# Chest_ECG.net
KiCad netlist of a schematic drawn in EAGLE
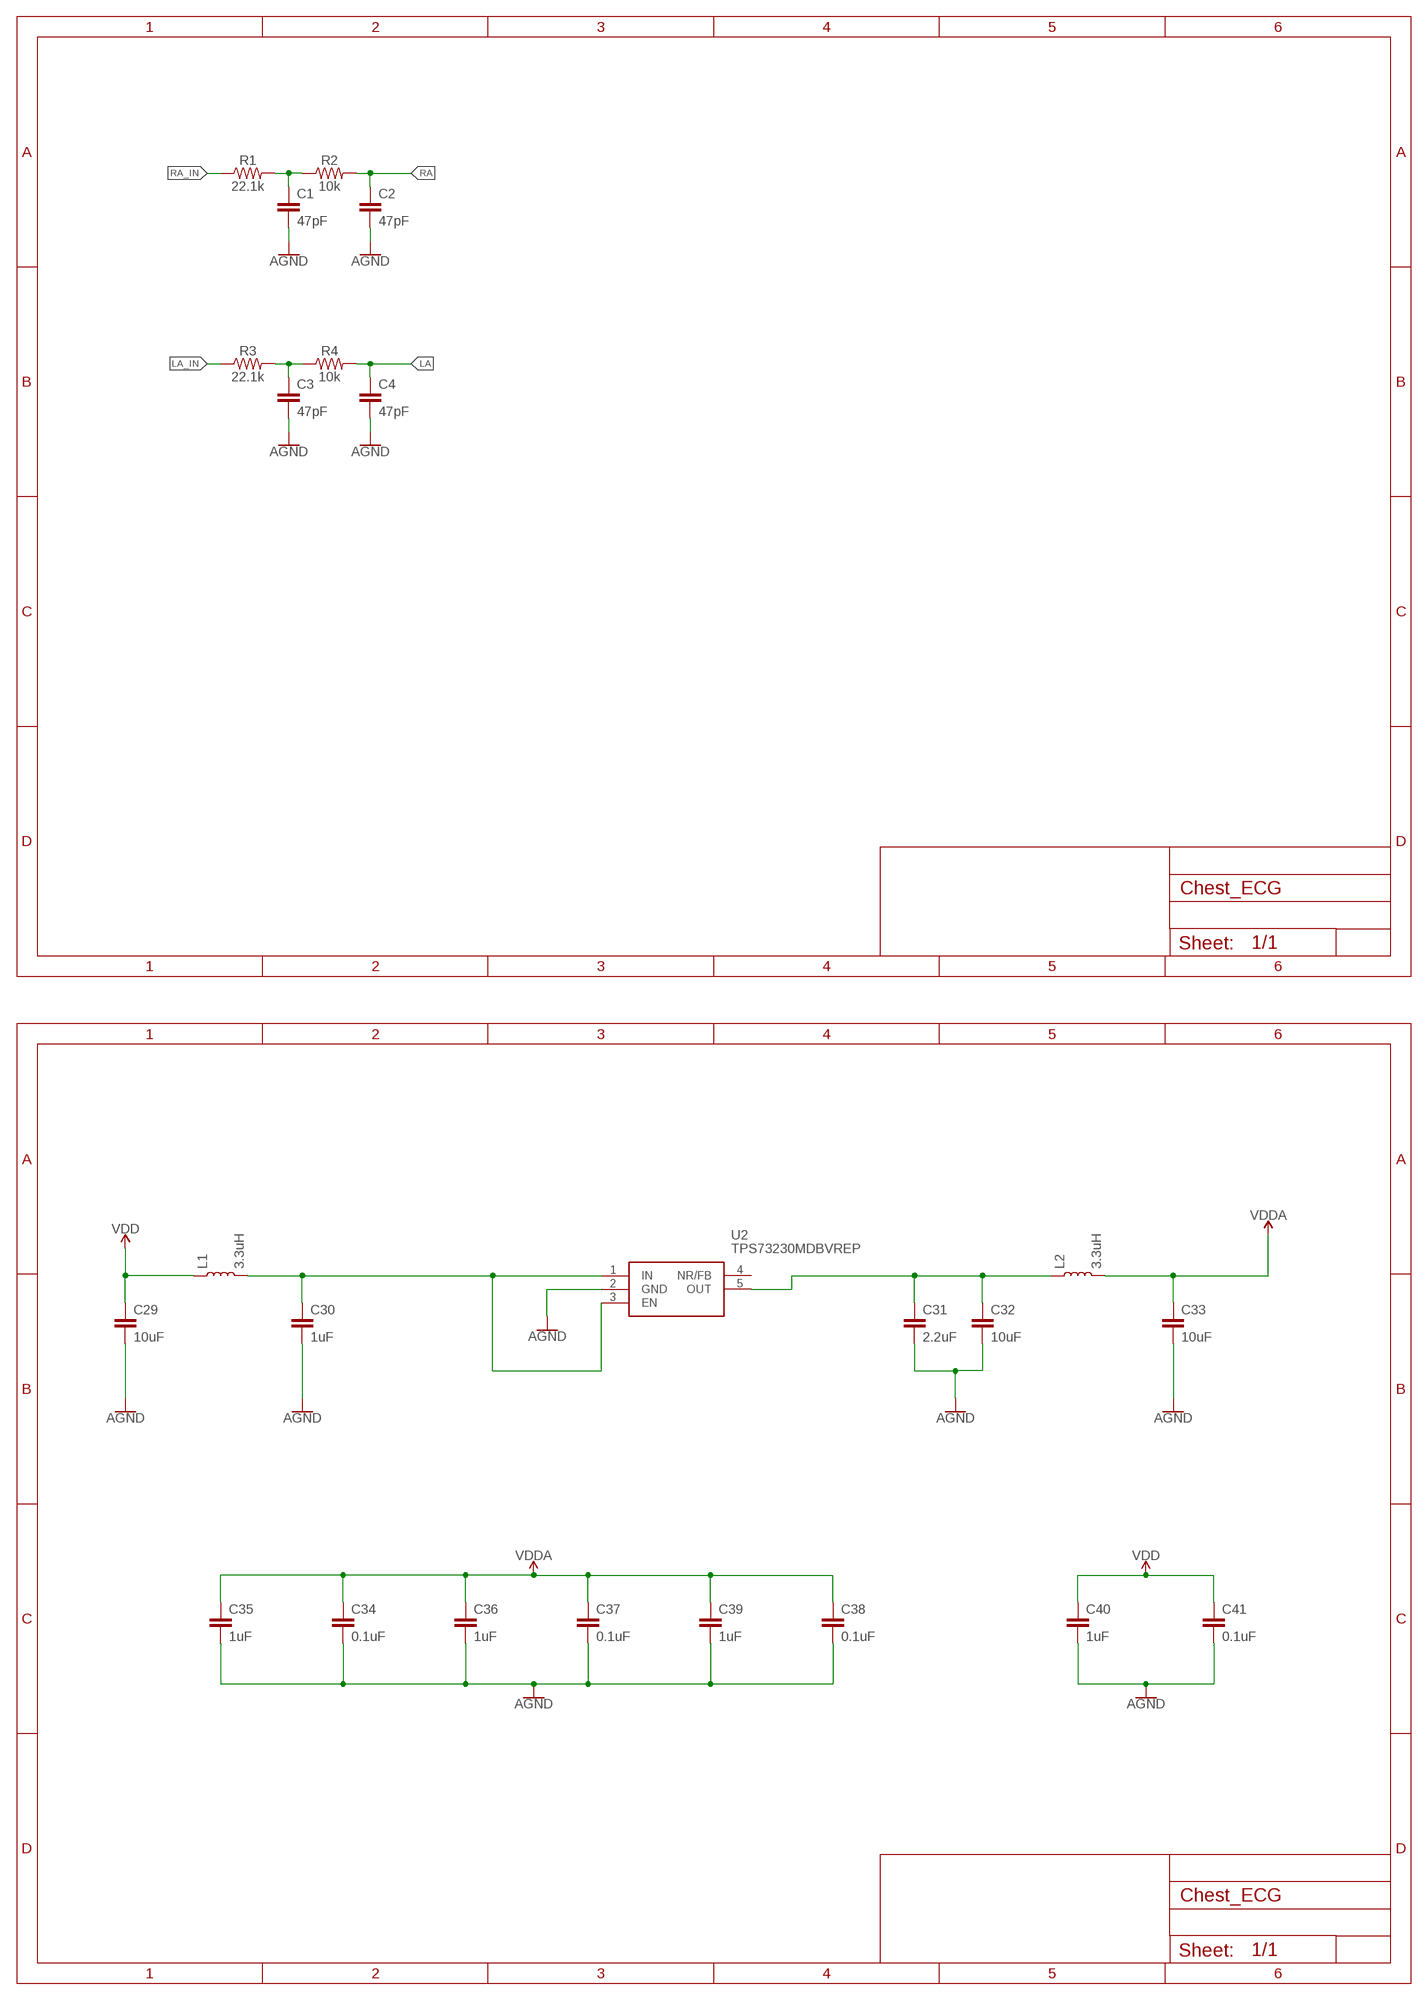
[diagram p0: schematic, sheet 1, part 1 of 2]
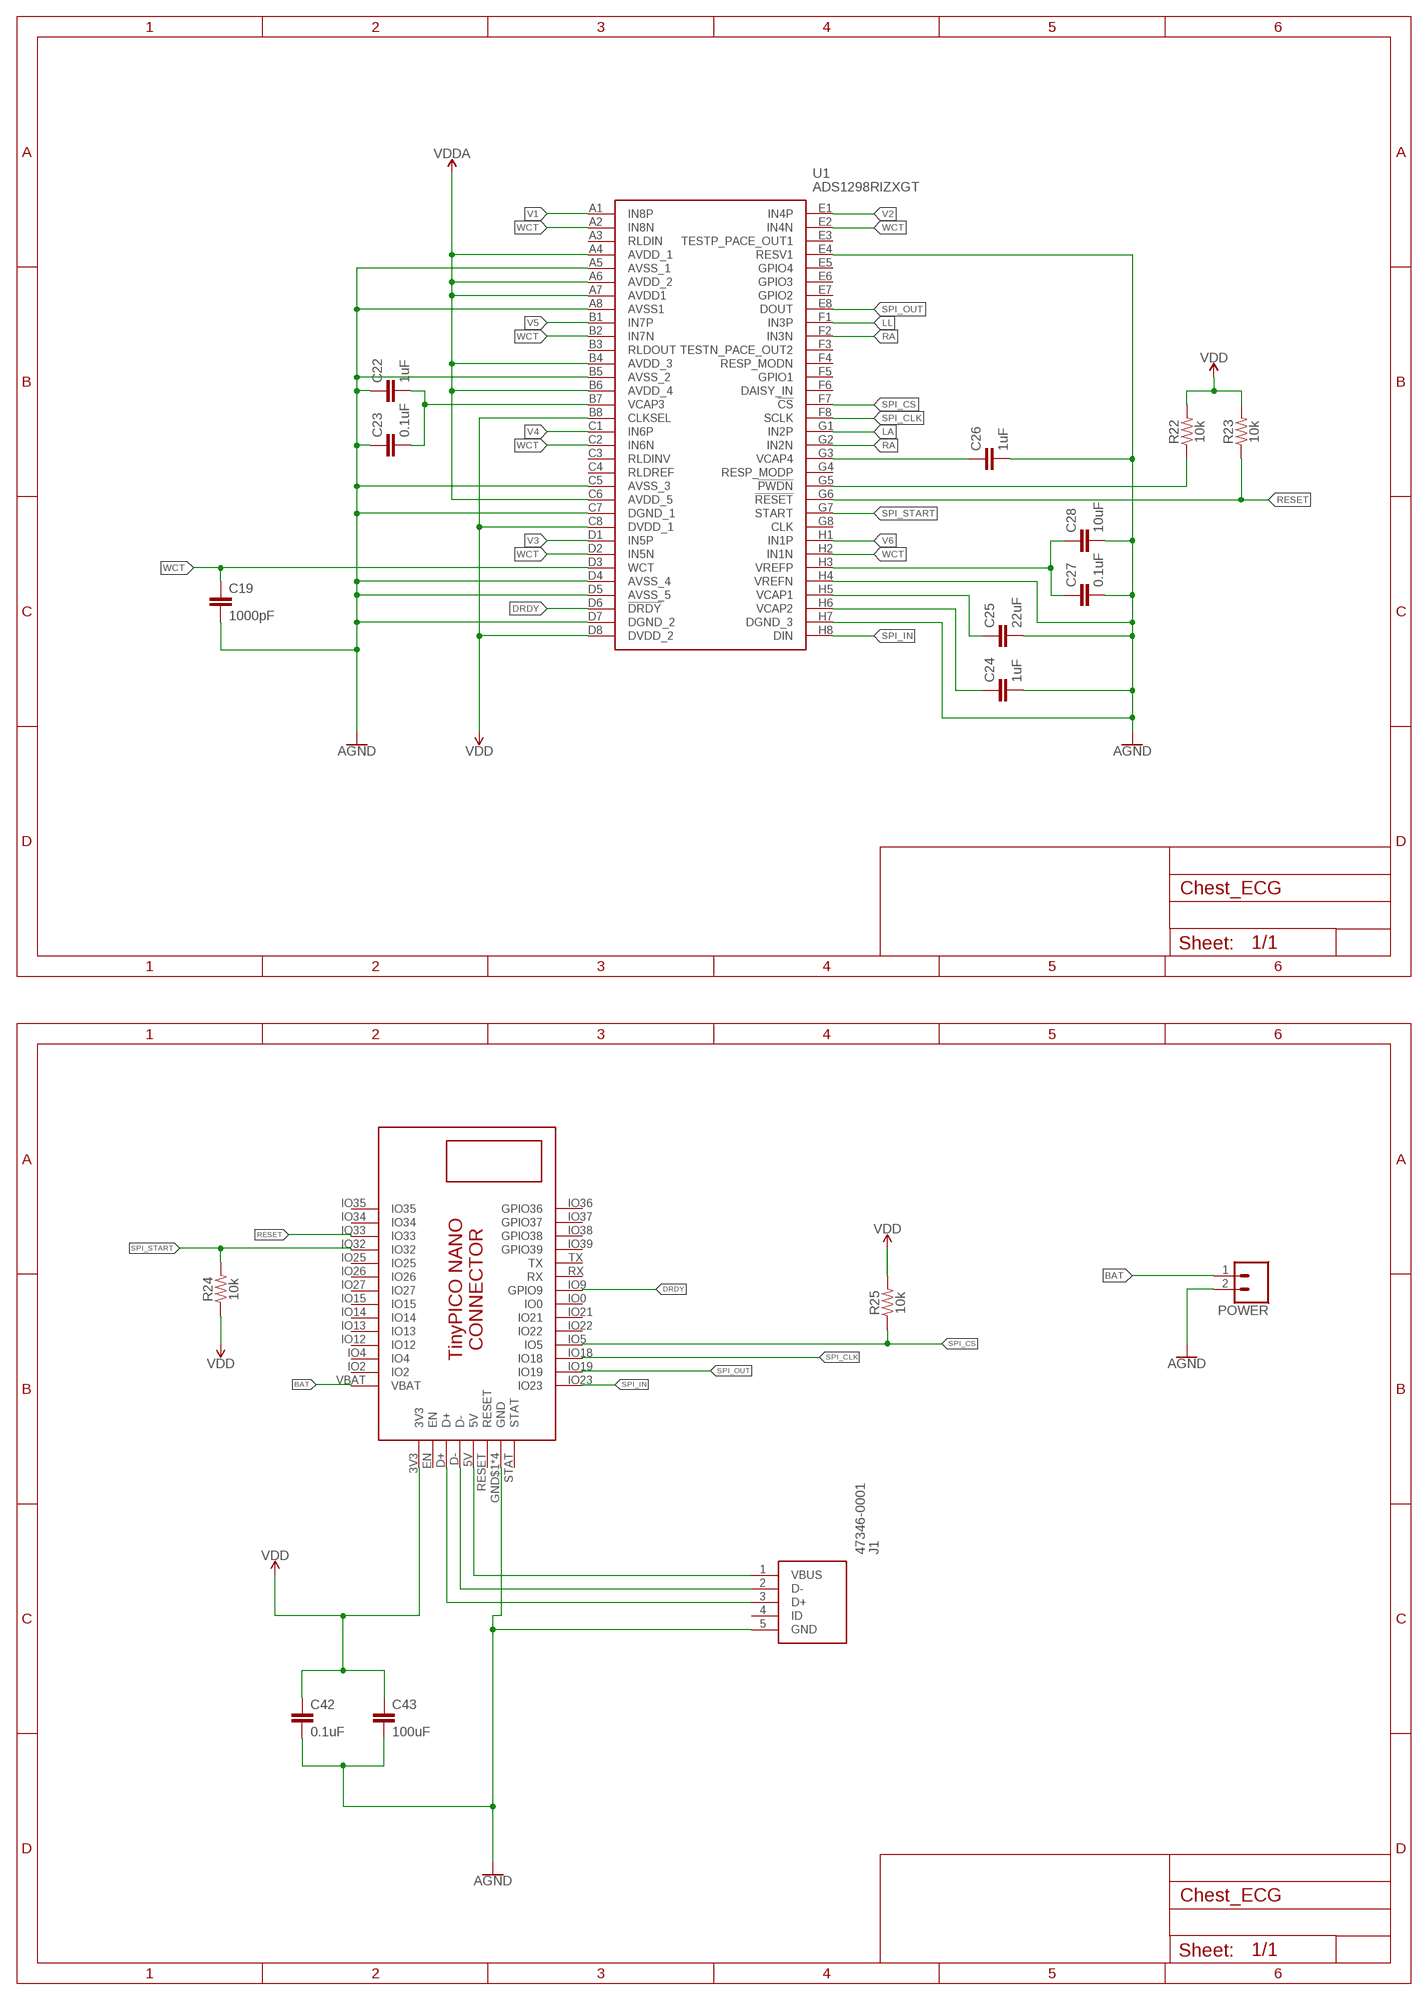
[diagram p1: schematic, sheet 1, part 2 of 2]

(export (version "E")
  (design (tool "Eeschema 10.0.6"))
  (components
    (comp (ref "C1")
      (value "47pF")
      (footprint "eagle-import:0603")
      (libsource (lib "eagle-import") (part "CAP-0603"))
    )
    (comp (ref "C2")
      (value "47pF")
      (footprint "eagle-import:0603")
      (libsource (lib "eagle-import") (part "CAP-0603"))
    )
    (comp (ref "C3")
      (value "47pF")
      (footprint "eagle-import:0603")
      (libsource (lib "eagle-import") (part "CAP-0603"))
    )
    (comp (ref "C4")
      (value "47pF")
      (footprint "eagle-import:0603")
      (libsource (lib "eagle-import") (part "CAP-0603"))
    )
    (comp (ref "C19")
      (value "1000pF")
      (footprint "eagle-import:0603")
      (libsource (lib "eagle-import") (part "CAP-0603"))
    )
    (comp (ref "C22")
      (value "1uF")
      (footprint "eagle-import:0603")
      (libsource (lib "eagle-import") (part "CAP-0603"))
    )
    (comp (ref "C23")
      (value "0.1uF")
      (footprint "eagle-import:0603")
      (libsource (lib "eagle-import") (part "CAP-0603"))
    )
    (comp (ref "C24")
      (value "1uF")
      (footprint "eagle-import:0603")
      (libsource (lib "eagle-import") (part "CAP-0603"))
    )
    (comp (ref "C25")
      (value "22uF")
      (footprint "eagle-import:0805")
      (libsource (lib "eagle-import") (part "CAP-0805"))
    )
    (comp (ref "C26")
      (value "1uF")
      (footprint "eagle-import:0603")
      (libsource (lib "eagle-import") (part "CAP-0603"))
    )
    (comp (ref "C27")
      (value "0.1uF")
      (footprint "eagle-import:0603")
      (libsource (lib "eagle-import") (part "CAP-0603"))
    )
    (comp (ref "C28")
      (value "10uF")
      (footprint "eagle-import:0805")
      (libsource (lib "eagle-import") (part "CAP-0805"))
    )
    (comp (ref "C29")
      (value "10uF")
      (footprint "eagle-import:0805")
      (libsource (lib "eagle-import") (part "CAP-0805"))
    )
    (comp (ref "C30")
      (value "1uF")
      (footprint "eagle-import:0603")
      (libsource (lib "eagle-import") (part "CAP-0603"))
    )
    (comp (ref "C31")
      (value "2.2uF")
      (footprint "eagle-import:0603")
      (libsource (lib "eagle-import") (part "CAP-0603"))
    )
    (comp (ref "C32")
      (value "10uF")
      (footprint "eagle-import:0805")
      (libsource (lib "eagle-import") (part "CAP-0805"))
    )
    (comp (ref "C33")
      (value "10uF")
      (footprint "eagle-import:0805")
      (libsource (lib "eagle-import") (part "CAP-0805"))
    )
    (comp (ref "C34")
      (value "0.1uF")
      (footprint "eagle-import:0603")
      (libsource (lib "eagle-import") (part "CAP-0603"))
    )
    (comp (ref "C35")
      (value "1uF")
      (footprint "eagle-import:0603")
      (libsource (lib "eagle-import") (part "CAP-0603"))
    )
    (comp (ref "C36")
      (value "1uF")
      (footprint "eagle-import:0603")
      (libsource (lib "eagle-import") (part "CAP-0603"))
    )
    (comp (ref "C37")
      (value "0.1uF")
      (footprint "eagle-import:0603")
      (libsource (lib "eagle-import") (part "CAP-0603"))
    )
    (comp (ref "C38")
      (value "0.1uF")
      (footprint "eagle-import:0603")
      (libsource (lib "eagle-import") (part "CAP-0603"))
    )
    (comp (ref "C39")
      (value "1uF")
      (footprint "eagle-import:0603")
      (libsource (lib "eagle-import") (part "CAP-0603"))
    )
    (comp (ref "C40")
      (value "1uF")
      (footprint "eagle-import:0603")
      (libsource (lib "eagle-import") (part "CAP-0603"))
    )
    (comp (ref "C41")
      (value "0.1uF")
      (footprint "eagle-import:0603")
      (libsource (lib "eagle-import") (part "CAP-0603"))
    )
    (comp (ref "C42")
      (value "0.1uF")
      (footprint "eagle-import:0603")
      (libsource (lib "eagle-import") (part "CAP-0603"))
    )
    (comp (ref "C43")
      (value "100uF")
      (footprint "eagle-import:0805")
      (libsource (lib "eagle-import") (part "CAP-0805"))
    )
    (comp (ref "J1")
      (value "47346-0001")
      (footprint "eagle-import:47346-0001")
      (fields (field (name "MOUSER_PART_NUMBER") "538-47346-0001"))
      (libsource (lib "eagle-import") (part "47346-0001"))
    )
    (comp (ref "L1")
      (value "3.3uH")
      (footprint "eagle-import:0805")
      (libsource (lib "eagle-import") (part "INDUCTOR-0805-3.3UH"))
    )
    (comp (ref "L2")
      (value "3.3uH")
      (footprint "eagle-import:0805")
      (libsource (lib "eagle-import") (part "INDUCTOR-0805-3.3UH"))
    )
    (comp (ref "POWER")
      (value "CONN_02")
      (footprint "eagle-import:1X02")
      (libsource (lib "eagle-import") (part "CONN_02"))
    )
    (comp (ref "R1")
      (value "22.1k")
      (footprint "eagle-import:0603")
      (libsource (lib "eagle-import") (part "RESISTOR0603"))
    )
    (comp (ref "R2")
      (value "10k")
      (footprint "eagle-import:0603")
      (libsource (lib "eagle-import") (part "RESISTOR0603"))
    )
    (comp (ref "R3")
      (value "22.1k")
      (footprint "eagle-import:0603")
      (libsource (lib "eagle-import") (part "RESISTOR0603"))
    )
    (comp (ref "R4")
      (value "10k")
      (footprint "eagle-import:0603")
      (libsource (lib "eagle-import") (part "RESISTOR0603"))
    )
    (comp (ref "R22")
      (value "10k")
      (footprint "eagle-import:0603")
      (libsource (lib "eagle-import") (part "RESISTOR0603"))
    )
    (comp (ref "R23")
      (value "10k")
      (footprint "eagle-import:0603")
      (libsource (lib "eagle-import") (part "RESISTOR0603"))
    )
    (comp (ref "R24")
      (value "10k")
      (footprint "eagle-import:0603")
      (libsource (lib "eagle-import") (part "RESISTOR0603"))
    )
    (comp (ref "R25")
      (value "10k")
      (footprint "eagle-import:0603")
      (libsource (lib "eagle-import") (part "RESISTOR0603"))
    )
    (comp (ref "U1")
      (value "ADS1298RIZXGT")
      (footprint "eagle-import:BGA64C80P8X8_800X800X145")
      (fields (field (name "MOUSER_PART_NUMBER") "595-ADS1298RIZXGT"))
      (libsource (lib "eagle-import") (part "ADS1298RIZXGT"))
    )
    (comp (ref "U2")
      (value "TPS73230MDBVREP")
      (footprint "eagle-import:SOT95P280X145-5N")
      (fields (field (name "MOUSER_PART_NUMBER") "595-TPS73230MDBVREP"))
      (libsource (lib "eagle-import") (part "TPS73230MDBVREP"))
    )
    (comp (ref "U3")
      (value "TINYPICO-NANO-CONNECTOR")
      (footprint "eagle-import:TINYPICO-NANO-CONNECTOR")
      (libsource (lib "eagle-import") (part "TINYPICO-NANO-CONNECTOR"))
    )
  )
  (nets
    (net (code "1") (name "AGND") (class "Default")
      (node (ref "C1") (pin "2") (pinfunction "2_2") (pintype "passive"))
      (node (ref "C19") (pin "2") (pinfunction "2_2") (pintype "passive"))
      (node (ref "C2") (pin "2") (pinfunction "2_2") (pintype "passive"))
      (node (ref "C22") (pin "1") (pinfunction "1_1") (pintype "passive"))
      (node (ref "C23") (pin "1") (pinfunction "1_1") (pintype "passive"))
      (node (ref "C24") (pin "2") (pinfunction "2_2") (pintype "passive"))
      (node (ref "C25") (pin "2") (pinfunction "2_2") (pintype "passive"))
      (node (ref "C26") (pin "2") (pinfunction "2_2") (pintype "passive"))
      (node (ref "C27") (pin "2") (pinfunction "2_2") (pintype "passive"))
      (node (ref "C28") (pin "2") (pinfunction "2_2") (pintype "passive"))
      (node (ref "C29") (pin "2") (pinfunction "2_2") (pintype "passive"))
      (node (ref "C3") (pin "2") (pinfunction "2_2") (pintype "passive"))
      (node (ref "C30") (pin "2") (pinfunction "2_2") (pintype "passive"))
      (node (ref "C31") (pin "2") (pinfunction "2_2") (pintype "passive"))
      (node (ref "C32") (pin "2") (pinfunction "2_2") (pintype "passive"))
      (node (ref "C33") (pin "2") (pinfunction "2_2") (pintype "passive"))
      (node (ref "C34") (pin "2") (pinfunction "2_2") (pintype "passive"))
      (node (ref "C35") (pin "2") (pinfunction "2_2") (pintype "passive"))
      (node (ref "C36") (pin "2") (pinfunction "2_2") (pintype "passive"))
      (node (ref "C37") (pin "2") (pinfunction "2_2") (pintype "passive"))
      (node (ref "C38") (pin "2") (pinfunction "2_2") (pintype "passive"))
      (node (ref "C39") (pin "2") (pinfunction "2_2") (pintype "passive"))
      (node (ref "C4") (pin "2") (pinfunction "2_2") (pintype "passive"))
      (node (ref "C40") (pin "2") (pinfunction "2_2") (pintype "passive"))
      (node (ref "C41") (pin "2") (pinfunction "2_2") (pintype "passive"))
      (node (ref "C42") (pin "2") (pinfunction "2_2") (pintype "passive"))
      (node (ref "C43") (pin "2") (pinfunction "2_2") (pintype "passive"))
      (node (ref "J1") (pin "5") (pinfunction "GND_5") (pintype "bidirectional"))
      (node (ref "POWER") (pin "2") (pinfunction "2_2") (pintype "passive"))
      (node (ref "U1") (pin "A5") (pinfunction "AVSS_1_A5") (pintype "bidirectional"))
      (node (ref "U1") (pin "A8") (pinfunction "AVSS1_A8") (pintype "bidirectional"))
      (node (ref "U1") (pin "B5") (pinfunction "AVSS_2_B5") (pintype "bidirectional"))
      (node (ref "U1") (pin "C5") (pinfunction "AVSS_3_C5") (pintype "bidirectional"))
      (node (ref "U1") (pin "C7") (pinfunction "DGND_1_C7") (pintype "bidirectional"))
      (node (ref "U1") (pin "D4") (pinfunction "AVSS_4_D4") (pintype "bidirectional"))
      (node (ref "U1") (pin "D5") (pinfunction "AVSS_5_D5") (pintype "bidirectional"))
      (node (ref "U1") (pin "D7") (pinfunction "DGND_2_D7") (pintype "bidirectional"))
      (node (ref "U1") (pin "E4") (pinfunction "RESV1_E4") (pintype "bidirectional"))
      (node (ref "U1") (pin "H4") (pinfunction "VREFN_H4") (pintype "bidirectional"))
      (node (ref "U1") (pin "H7") (pinfunction "DGND_3_H7") (pintype "bidirectional"))
      (node (ref "U2") (pin "2") (pinfunction "GND_2") (pintype "bidirectional"))
      (node (ref "U3") (pin "GND$1") (pinfunction "GND_GND$1") (pintype "power_in"))
      (node (ref "U3") (pin "GND$2") (pinfunction "GND_GND$2") (pintype "power_in"))
      (node (ref "U3") (pin "GND$3") (pinfunction "GND_GND$3") (pintype "power_in"))
      (node (ref "U3") (pin "GND$4") (pinfunction "GND_GND$4") (pintype "power_in"))
    )
    (net (code "2") (name "BAT") (class "Default")
      (node (ref "POWER") (pin "1") (pinfunction "1_1") (pintype "passive"))
      (node (ref "U3") (pin "VBAT") (pinfunction "VBAT_VBAT") (pintype "power_in"))
    )
    (net (code "3") (name "DRDY") (class "Default")
      (node (ref "U1") (pin "D6") (pinfunction "~{DRDY}_D6") (pintype "bidirectional"))
      (node (ref "U3") (pin "IO9") (pinfunction "GPIO9_IO9") (pintype "bidirectional"))
    )
    (net (code "4") (name "LA") (class "Default")
      (node (ref "C4") (pin "1") (pinfunction "1_1") (pintype "passive"))
      (node (ref "R4") (pin "2") (pinfunction "2_2") (pintype "passive"))
      (node (ref "U1") (pin "G1") (pinfunction "IN2P_G1") (pintype "bidirectional"))
    )
    (net (code "5") (name "LA_IN") (class "Default")
      (node (ref "R3") (pin "1") (pinfunction "1_1") (pintype "passive"))
    )
    (net (code "6") (name "LL") (class "Default")
      (node (ref "U1") (pin "F1") (pinfunction "IN3P_F1") (pintype "bidirectional"))
    )
    (net (code "7") (name "Net-(C1-Pad1)") (class "Default")
      (node (ref "C1") (pin "1") (pinfunction "1_1") (pintype "passive"))
      (node (ref "R1") (pin "2") (pinfunction "2_2") (pintype "passive"))
      (node (ref "R2") (pin "1") (pinfunction "1_1") (pintype "passive"))
    )
    (net (code "8") (name "Net-(C3-Pad1)") (class "Default")
      (node (ref "C3") (pin "1") (pinfunction "1_1") (pintype "passive"))
      (node (ref "R3") (pin "2") (pinfunction "2_2") (pintype "passive"))
      (node (ref "R4") (pin "1") (pinfunction "1_1") (pintype "passive"))
    )
    (net (code "9") (name "Net-(J1-D+)") (class "Default")
      (node (ref "J1") (pin "3") (pinfunction "D+_3") (pintype "bidirectional"))
      (node (ref "U3") (pin "D+") (pinfunction "D+_D+") (pintype "bidirectional"))
    )
    (net (code "10") (name "Net-(J1-D-)") (class "Default")
      (node (ref "J1") (pin "2") (pinfunction "D-_2") (pintype "bidirectional"))
      (node (ref "U3") (pin "D-") (pinfunction "D-_D-") (pintype "bidirectional"))
    )
    (net (code "11") (name "Net-(J1-VBUS)") (class "Default")
      (node (ref "J1") (pin "1") (pinfunction "VBUS_1") (pintype "bidirectional"))
      (node (ref "U3") (pin "5V") (pinfunction "5V_5V") (pintype "power_in"))
    )
    (net (code "12") (name "Net-(U1-VCAP1)") (class "Default")
      (node (ref "C25") (pin "1") (pinfunction "1_1") (pintype "passive"))
      (node (ref "U1") (pin "H5") (pinfunction "VCAP1_H5") (pintype "bidirectional"))
    )
    (net (code "13") (name "Net-(U1-VCAP2)") (class "Default")
      (node (ref "C24") (pin "1") (pinfunction "1_1") (pintype "passive"))
      (node (ref "U1") (pin "H6") (pinfunction "VCAP2_H6") (pintype "bidirectional"))
    )
    (net (code "14") (name "Net-(U1-VCAP3)") (class "Default")
      (node (ref "C22") (pin "2") (pinfunction "2_2") (pintype "passive"))
      (node (ref "C23") (pin "2") (pinfunction "2_2") (pintype "passive"))
      (node (ref "U1") (pin "B7") (pinfunction "VCAP3_B7") (pintype "bidirectional"))
    )
    (net (code "15") (name "Net-(U1-VCAP4)") (class "Default")
      (node (ref "C26") (pin "1") (pinfunction "1_1") (pintype "passive"))
      (node (ref "U1") (pin "G3") (pinfunction "VCAP4_G3") (pintype "bidirectional"))
    )
    (net (code "16") (name "Net-(U1-VREFP)") (class "Default")
      (node (ref "C27") (pin "1") (pinfunction "1_1") (pintype "passive"))
      (node (ref "C28") (pin "1") (pinfunction "1_1") (pintype "passive"))
      (node (ref "U1") (pin "H3") (pinfunction "VREFP_H3") (pintype "bidirectional"))
    )
    (net (code "17") (name "Net-(U1-~{PWDN})") (class "Default")
      (node (ref "R22") (pin "1") (pinfunction "1_1") (pintype "passive"))
      (node (ref "U1") (pin "G5") (pinfunction "~{PWDN}_G5") (pintype "bidirectional"))
    )
    (net (code "18") (name "Net-(U2-EN)") (class "Default")
      (node (ref "C30") (pin "1") (pinfunction "1_1") (pintype "passive"))
      (node (ref "L1") (pin "2") (pinfunction "2_2") (pintype "passive"))
      (node (ref "U2") (pin "1") (pinfunction "IN_1") (pintype "bidirectional"))
      (node (ref "U2") (pin "3") (pinfunction "EN_3") (pintype "bidirectional"))
    )
    (net (code "19") (name "Net-(U2-OUT)") (class "Default")
      (node (ref "C31") (pin "1") (pinfunction "1_1") (pintype "passive"))
      (node (ref "C32") (pin "1") (pinfunction "1_1") (pintype "passive"))
      (node (ref "L2") (pin "1") (pinfunction "1_1") (pintype "passive"))
      (node (ref "U2") (pin "5") (pinfunction "OUT_5") (pintype "bidirectional"))
    )
    (net (code "20") (name "RA") (class "Default")
      (node (ref "C2") (pin "1") (pinfunction "1_1") (pintype "passive"))
      (node (ref "R2") (pin "2") (pinfunction "2_2") (pintype "passive"))
      (node (ref "U1") (pin "F2") (pinfunction "IN3N_F2") (pintype "bidirectional"))
      (node (ref "U1") (pin "G2") (pinfunction "IN2N_G2") (pintype "bidirectional"))
    )
    (net (code "21") (name "RA_IN") (class "Default")
      (node (ref "R1") (pin "1") (pinfunction "1_1") (pintype "passive"))
    )
    (net (code "22") (name "RESET") (class "Default")
      (node (ref "R23") (pin "1") (pinfunction "1_1") (pintype "passive"))
      (node (ref "U1") (pin "G6") (pinfunction "~{RESET}_G6") (pintype "bidirectional"))
      (node (ref "U3") (pin "IO33") (pinfunction "IO33_IO33") (pintype "bidirectional"))
    )
    (net (code "23") (name "SPI_CLK") (class "Default")
      (node (ref "U1") (pin "F8") (pinfunction "SCLK_F8") (pintype "bidirectional"))
      (node (ref "U3") (pin "IO18") (pinfunction "IO18_IO18") (pintype "bidirectional"))
    )
    (net (code "24") (name "SPI_CS") (class "Default")
      (node (ref "R25") (pin "1") (pinfunction "1_1") (pintype "passive"))
      (node (ref "U1") (pin "F7") (pinfunction "~{CS}_F7") (pintype "bidirectional"))
      (node (ref "U3") (pin "IO5") (pinfunction "IO5_IO5") (pintype "bidirectional"))
    )
    (net (code "25") (name "SPI_IN") (class "Default")
      (node (ref "U1") (pin "H8") (pinfunction "DIN_H8") (pintype "bidirectional"))
      (node (ref "U3") (pin "IO23") (pinfunction "IO23_IO23") (pintype "bidirectional"))
    )
    (net (code "26") (name "SPI_OUT") (class "Default")
      (node (ref "U1") (pin "E8") (pinfunction "DOUT_E8") (pintype "bidirectional"))
      (node (ref "U3") (pin "IO19") (pinfunction "IO19_IO19") (pintype "bidirectional"))
    )
    (net (code "27") (name "SPI_START") (class "Default")
      (node (ref "R24") (pin "2") (pinfunction "2_2") (pintype "passive"))
      (node (ref "U1") (pin "G7") (pinfunction "START_G7") (pintype "bidirectional"))
      (node (ref "U3") (pin "IO32") (pinfunction "IO32_IO32") (pintype "bidirectional"))
    )
    (net (code "28") (name "V1") (class "Default")
      (node (ref "U1") (pin "A1") (pinfunction "IN8P_A1") (pintype "bidirectional"))
    )
    (net (code "29") (name "V2") (class "Default")
      (node (ref "U1") (pin "E1") (pinfunction "IN4P_E1") (pintype "bidirectional"))
    )
    (net (code "30") (name "V3") (class "Default")
      (node (ref "U1") (pin "D1") (pinfunction "IN5P_D1") (pintype "bidirectional"))
    )
    (net (code "31") (name "V4") (class "Default")
      (node (ref "U1") (pin "C1") (pinfunction "IN6P_C1") (pintype "bidirectional"))
    )
    (net (code "32") (name "V5") (class "Default")
      (node (ref "U1") (pin "B1") (pinfunction "IN7P_B1") (pintype "bidirectional"))
    )
    (net (code "33") (name "V6") (class "Default")
      (node (ref "U1") (pin "H1") (pinfunction "IN1P_H1") (pintype "bidirectional"))
    )
    (net (code "34") (name "VDD") (class "Default")
      (node (ref "C29") (pin "1") (pinfunction "1_1") (pintype "passive"))
      (node (ref "C40") (pin "1") (pinfunction "1_1") (pintype "passive"))
      (node (ref "C41") (pin "1") (pinfunction "1_1") (pintype "passive"))
      (node (ref "C42") (pin "1") (pinfunction "1_1") (pintype "passive"))
      (node (ref "C43") (pin "1") (pinfunction "1_1") (pintype "passive"))
      (node (ref "L1") (pin "1") (pinfunction "1_1") (pintype "passive"))
      (node (ref "R22") (pin "2") (pinfunction "2_2") (pintype "passive"))
      (node (ref "R23") (pin "2") (pinfunction "2_2") (pintype "passive"))
      (node (ref "R24") (pin "1") (pinfunction "1_1") (pintype "passive"))
      (node (ref "R25") (pin "2") (pinfunction "2_2") (pintype "passive"))
      (node (ref "U1") (pin "B8") (pinfunction "CLKSEL_B8") (pintype "bidirectional"))
      (node (ref "U1") (pin "C8") (pinfunction "DVDD_1_C8") (pintype "bidirectional"))
      (node (ref "U1") (pin "D8") (pinfunction "DVDD_2_D8") (pintype "bidirectional"))
      (node (ref "U3") (pin "3V3") (pinfunction "3V3_3V3") (pintype "power_in"))
    )
    (net (code "35") (name "VDDA") (class "Default")
      (node (ref "C33") (pin "1") (pinfunction "1_1") (pintype "passive"))
      (node (ref "C34") (pin "1") (pinfunction "1_1") (pintype "passive"))
      (node (ref "C35") (pin "1") (pinfunction "1_1") (pintype "passive"))
      (node (ref "C36") (pin "1") (pinfunction "1_1") (pintype "passive"))
      (node (ref "C37") (pin "1") (pinfunction "1_1") (pintype "passive"))
      (node (ref "C38") (pin "1") (pinfunction "1_1") (pintype "passive"))
      (node (ref "C39") (pin "1") (pinfunction "1_1") (pintype "passive"))
      (node (ref "L2") (pin "2") (pinfunction "2_2") (pintype "passive"))
      (node (ref "U1") (pin "A4") (pinfunction "AVDD_1_A4") (pintype "bidirectional"))
      (node (ref "U1") (pin "A6") (pinfunction "AVDD_2_A6") (pintype "bidirectional"))
      (node (ref "U1") (pin "A7") (pinfunction "AVDD1_A7") (pintype "bidirectional"))
      (node (ref "U1") (pin "B4") (pinfunction "AVDD_3_B4") (pintype "bidirectional"))
      (node (ref "U1") (pin "B6") (pinfunction "AVDD_4_B6") (pintype "bidirectional"))
      (node (ref "U1") (pin "C6") (pinfunction "AVDD_5_C6") (pintype "bidirectional"))
    )
    (net (code "36") (name "WCT") (class "Default")
      (node (ref "C19") (pin "1") (pinfunction "1_1") (pintype "passive"))
      (node (ref "U1") (pin "A2") (pinfunction "IN8N_A2") (pintype "bidirectional"))
      (node (ref "U1") (pin "B2") (pinfunction "IN7N_B2") (pintype "bidirectional"))
      (node (ref "U1") (pin "C2") (pinfunction "IN6N_C2") (pintype "bidirectional"))
      (node (ref "U1") (pin "D2") (pinfunction "IN5N_D2") (pintype "bidirectional"))
      (node (ref "U1") (pin "D3") (pinfunction "WCT_D3") (pintype "bidirectional"))
      (node (ref "U1") (pin "E2") (pinfunction "IN4N_E2") (pintype "bidirectional"))
      (node (ref "U1") (pin "H2") (pinfunction "IN1N_H2") (pintype "bidirectional"))
    )
    (net (code "37") (name "unconnected-(J1-ID-Pad4)") (class "Default")
      (node (ref "J1") (pin "4") (pinfunction "ID_4") (pintype "bidirectional"))
    )
    (net (code "38") (name "unconnected-(U1-CLK-PadG8)") (class "Default")
      (node (ref "U1") (pin "G8") (pinfunction "CLK_G8") (pintype "bidirectional"))
    )
    (net (code "39") (name "unconnected-(U1-DAISY_IN-PadF6)") (class "Default")
      (node (ref "U1") (pin "F6") (pinfunction "DAISY_IN_F6") (pintype "bidirectional"))
    )
    (net (code "40") (name "unconnected-(U1-GPIO1-PadF5)") (class "Default")
      (node (ref "U1") (pin "F5") (pinfunction "GPIO1_F5") (pintype "bidirectional"))
    )
    (net (code "41") (name "unconnected-(U1-GPIO2-PadE7)") (class "Default")
      (node (ref "U1") (pin "E7") (pinfunction "GPIO2_E7") (pintype "bidirectional"))
    )
    (net (code "42") (name "unconnected-(U1-GPIO3-PadE6)") (class "Default")
      (node (ref "U1") (pin "E6") (pinfunction "GPIO3_E6") (pintype "bidirectional"))
    )
    (net (code "43") (name "unconnected-(U1-GPIO4-PadE5)") (class "Default")
      (node (ref "U1") (pin "E5") (pinfunction "GPIO4_E5") (pintype "bidirectional"))
    )
    (net (code "44") (name "unconnected-(U1-RESP_MODN-PadF4)") (class "Default")
      (node (ref "U1") (pin "F4") (pinfunction "RESP_MODN_F4") (pintype "bidirectional"))
    )
    (net (code "45") (name "unconnected-(U1-RESP_MODP-PadG4)") (class "Default")
      (node (ref "U1") (pin "G4") (pinfunction "RESP_MODP_G4") (pintype "bidirectional"))
    )
    (net (code "46") (name "unconnected-(U1-RLDIN-PadA3)") (class "Default")
      (node (ref "U1") (pin "A3") (pinfunction "RLDIN_A3") (pintype "bidirectional"))
    )
    (net (code "47") (name "unconnected-(U1-RLDINV-PadC3)") (class "Default")
      (node (ref "U1") (pin "C3") (pinfunction "RLDINV_C3") (pintype "bidirectional"))
    )
    (net (code "48") (name "unconnected-(U1-RLDOUT-PadB3)") (class "Default")
      (node (ref "U1") (pin "B3") (pinfunction "RLDOUT_B3") (pintype "bidirectional"))
    )
    (net (code "49") (name "unconnected-(U1-RLDREF-PadC4)") (class "Default")
      (node (ref "U1") (pin "C4") (pinfunction "RLDREF_C4") (pintype "bidirectional"))
    )
    (net (code "50") (name "unconnected-(U1-TESTN_PACE_OUT2-PadF3)") (class "Default")
      (node (ref "U1") (pin "F3") (pinfunction "TESTN_PACE_OUT2_F3") (pintype "bidirectional"))
    )
    (net (code "51") (name "unconnected-(U1-TESTP_PACE_OUT1-PadE3)") (class "Default")
      (node (ref "U1") (pin "E3") (pinfunction "TESTP_PACE_OUT1_E3") (pintype "bidirectional"))
    )
    (net (code "52") (name "unconnected-(U2-NR{slash}FB-Pad4)") (class "Default")
      (node (ref "U2") (pin "4") (pinfunction "NR/FB_4") (pintype "bidirectional"))
    )
    (net (code "53") (name "unconnected-(U3-GPIO36-PadIO36)") (class "Default")
      (node (ref "U3") (pin "IO36") (pinfunction "GPIO36_IO36") (pintype "bidirectional"))
    )
    (net (code "54") (name "unconnected-(U3-GPIO37-PadIO37)") (class "Default")
      (node (ref "U3") (pin "IO37") (pinfunction "GPIO37_IO37") (pintype "bidirectional"))
    )
    (net (code "55") (name "unconnected-(U3-GPIO38-PadIO38)") (class "Default")
      (node (ref "U3") (pin "IO38") (pinfunction "GPIO38_IO38") (pintype "bidirectional"))
    )
    (net (code "56") (name "unconnected-(U3-GPIO39-PadIO39)") (class "Default")
      (node (ref "U3") (pin "IO39") (pinfunction "GPIO39_IO39") (pintype "bidirectional"))
    )
    (net (code "57") (name "unconnected-(U3-PadEN)") (class "Default")
      (node (ref "U3") (pin "EN") (pinfunction "EN_EN") (pintype "input"))
    )
    (net (code "58") (name "unconnected-(U3-PadIO0)") (class "Default")
      (node (ref "U3") (pin "IO0") (pinfunction "IO0_IO0") (pintype "bidirectional"))
    )
    (net (code "59") (name "unconnected-(U3-PadIO2)") (class "Default")
      (node (ref "U3") (pin "IO2") (pinfunction "IO2_IO2") (pintype "bidirectional"))
    )
    (net (code "60") (name "unconnected-(U3-PadIO4)") (class "Default")
      (node (ref "U3") (pin "IO4") (pinfunction "IO4_IO4") (pintype "bidirectional"))
    )
    (net (code "61") (name "unconnected-(U3-PadIO12)") (class "Default")
      (node (ref "U3") (pin "IO12") (pinfunction "IO12_IO12") (pintype "bidirectional"))
    )
    (net (code "62") (name "unconnected-(U3-PadIO13)") (class "Default")
      (node (ref "U3") (pin "IO13") (pinfunction "IO13_IO13") (pintype "bidirectional"))
    )
    (net (code "63") (name "unconnected-(U3-PadIO14)") (class "Default")
      (node (ref "U3") (pin "IO14") (pinfunction "IO14_IO14") (pintype "bidirectional"))
    )
    (net (code "64") (name "unconnected-(U3-PadIO15)") (class "Default")
      (node (ref "U3") (pin "IO15") (pinfunction "IO15_IO15") (pintype "bidirectional"))
    )
    (net (code "65") (name "unconnected-(U3-PadIO21)") (class "Default")
      (node (ref "U3") (pin "IO21") (pinfunction "IO21_IO21") (pintype "bidirectional"))
    )
    (net (code "66") (name "unconnected-(U3-PadIO22)") (class "Default")
      (node (ref "U3") (pin "IO22") (pinfunction "IO22_IO22") (pintype "bidirectional"))
    )
    (net (code "67") (name "unconnected-(U3-PadIO25)") (class "Default")
      (node (ref "U3") (pin "IO25") (pinfunction "IO25_IO25") (pintype "bidirectional"))
    )
    (net (code "68") (name "unconnected-(U3-PadIO26)") (class "Default")
      (node (ref "U3") (pin "IO26") (pinfunction "IO26_IO26") (pintype "bidirectional"))
    )
    (net (code "69") (name "unconnected-(U3-PadIO27)") (class "Default")
      (node (ref "U3") (pin "IO27") (pinfunction "IO27_IO27") (pintype "bidirectional"))
    )
    (net (code "70") (name "unconnected-(U3-PadIO34)") (class "Default")
      (node (ref "U3") (pin "IO34") (pinfunction "IO34_IO34") (pintype "bidirectional"))
    )
    (net (code "71") (name "unconnected-(U3-PadIO35)") (class "Default")
      (node (ref "U3") (pin "IO35") (pinfunction "IO35_IO35") (pintype "bidirectional"))
    )
    (net (code "72") (name "unconnected-(U3-PadRESET)") (class "Default")
      (node (ref "U3") (pin "RESET") (pinfunction "RESET_RESET") (pintype "bidirectional"))
    )
    (net (code "73") (name "unconnected-(U3-PadRX)") (class "Default")
      (node (ref "U3") (pin "RX") (pinfunction "RX_RX") (pintype "bidirectional"))
    )
    (net (code "74") (name "unconnected-(U3-PadSTAT)") (class "Default")
      (node (ref "U3") (pin "STAT") (pinfunction "STAT_STAT") (pintype "output"))
    )
    (net (code "75") (name "unconnected-(U3-PadTX)") (class "Default")
      (node (ref "U3") (pin "TX") (pinfunction "TX_TX") (pintype "bidirectional"))
    )
  )
)
